# LNShield.net
KiCad netlist of a schematic drawn in EAGLE
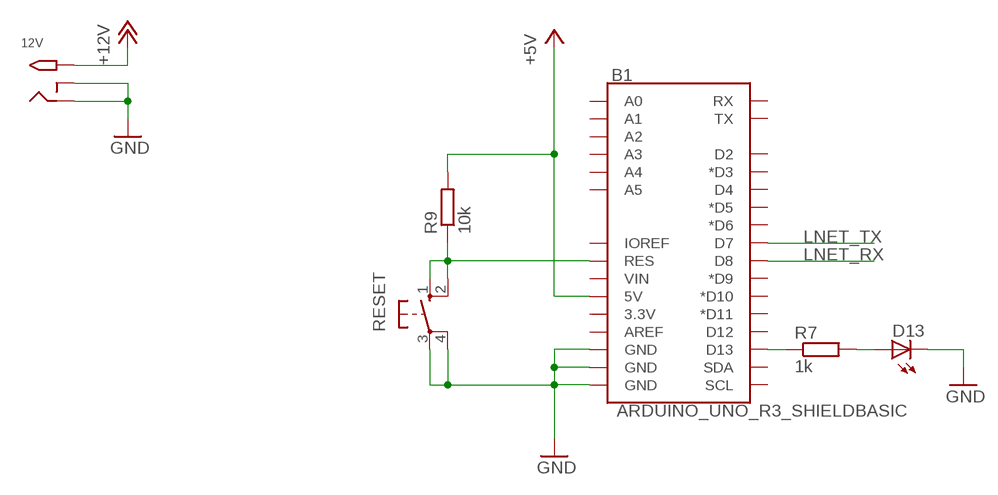
[diagram p0: schematic, sheet 1]
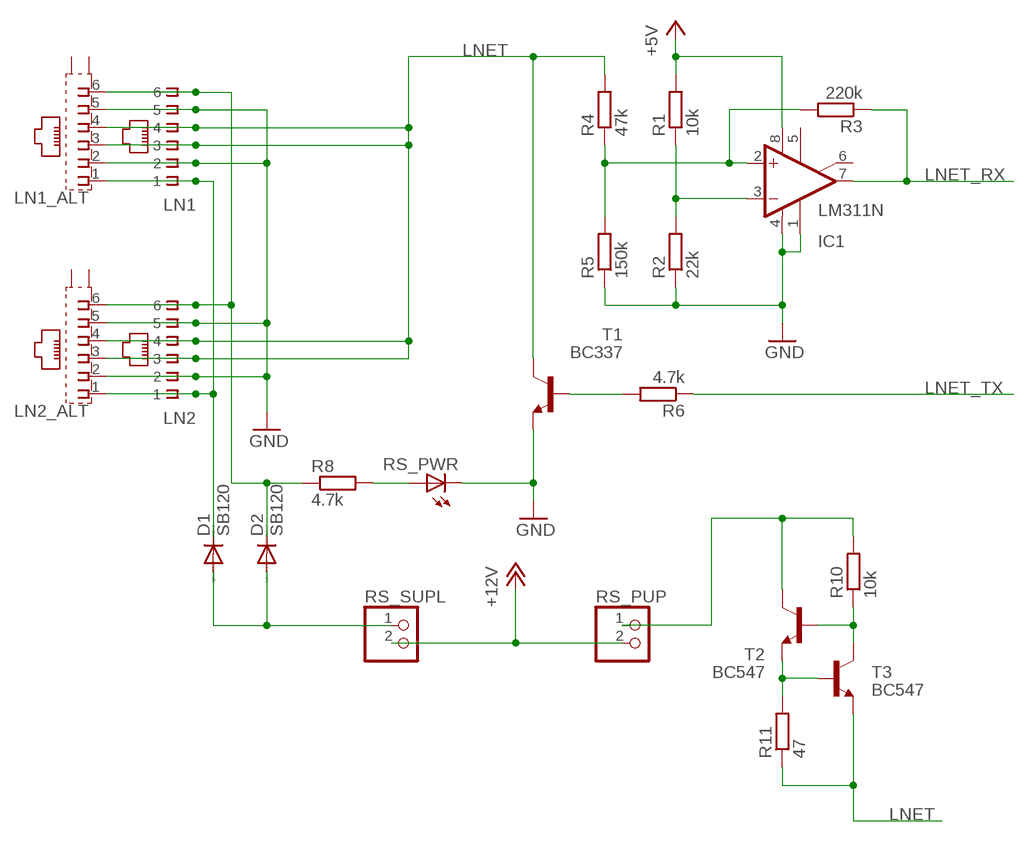
[diagram p1: schematic, sheet 2]

(export (version "E")
  (design (tool "Eeschema 10.0.6"))
  (components
    (comp (ref "12V")
      (value "2.1MMJACKTHM")
      (footprint "eagle-import:PJ-102A")
      (libsource (lib "eagle-import") (part "2.1MMJACKTHM"))
    )
    (comp (ref "B1")
      (value "ARDUINO_UNO_R3_SHIELDBASIC")
      (footprint "eagle-import:UNO_R3_SHIELD")
      (libsource (lib "eagle-import") (part "ARDUINO_UNO_R3_SHIELDBASIC"))
    )
    (comp (ref "D13")
      (value "LED3MM")
      (footprint "eagle-import:LED3MM")
      (libsource (lib "eagle-import") (part "LED3MM"))
    )
    (comp (ref "R7")
      (value "1k")
      (footprint "eagle-import:0207_2V")
      (libsource (lib "eagle-import") (part "R-EU_0207/2V"))
    )
    (comp (ref "R9")
      (value "10k")
      (footprint "eagle-import:0207_2V")
      (libsource (lib "eagle-import") (part "R-EU_0207/2V"))
    )
    (comp (ref "RESET")
      (value "10-XX")
      (footprint "eagle-import:B3F-10XX")
      (fields (field (name "MPN") "B3F-1000"))
      (libsource (lib "eagle-import") (part "10-XX"))
    )
    (comp (ref "D1")
      (value "SB120")
      (footprint "eagle-import:DO41-10")
      (libsource (lib "eagle-import") (part "SB120"))
    )
    (comp (ref "D2")
      (value "SB120")
      (footprint "eagle-import:DO41-10")
      (libsource (lib "eagle-import") (part "SB120"))
    )
    (comp (ref "IC1")
      (value "LM311N")
      (footprint "eagle-import:DIL08")
      (libsource (lib "eagle-import") (part "LM311N"))
    )
    (comp (ref "LN1")
      (value "RJ11-6X")
      (footprint "eagle-import:RJ11-NO_SHIELD")
      (libsource (lib "eagle-import") (part "RJ11-6X"))
    )
    (comp (ref "LN1_ALT")
      (value "YH-55-10")
      (footprint "eagle-import:YH-55-10")
      (libsource (lib "eagle-import") (part "YH-55-10"))
    )
    (comp (ref "LN2")
      (value "RJ11-6X")
      (footprint "eagle-import:RJ11-NO_SHIELD")
      (libsource (lib "eagle-import") (part "RJ11-6X"))
    )
    (comp (ref "LN2_ALT")
      (value "YH-55-10")
      (footprint "eagle-import:YH-55-10")
      (libsource (lib "eagle-import") (part "YH-55-10"))
    )
    (comp (ref "R1")
      (value "10k")
      (footprint "eagle-import:0207_2V")
      (libsource (lib "eagle-import") (part "R-EU_0207/2V"))
    )
    (comp (ref "R2")
      (value "22k")
      (footprint "eagle-import:0207_2V")
      (libsource (lib "eagle-import") (part "R-EU_0207/2V"))
    )
    (comp (ref "R3")
      (value "220k")
      (footprint "eagle-import:0207_2V")
      (libsource (lib "eagle-import") (part "R-EU_0207/2V"))
    )
    (comp (ref "R4")
      (value "47k")
      (footprint "eagle-import:0207_2V")
      (libsource (lib "eagle-import") (part "R-EU_0207/2V"))
    )
    (comp (ref "R5")
      (value "150k")
      (footprint "eagle-import:0207_2V")
      (libsource (lib "eagle-import") (part "R-EU_0207/2V"))
    )
    (comp (ref "R6")
      (value "4.7k")
      (footprint "eagle-import:0207_2V")
      (libsource (lib "eagle-import") (part "R-EU_0207/2V"))
    )
    (comp (ref "R8")
      (value "4.7k")
      (footprint "eagle-import:0207_2V")
      (libsource (lib "eagle-import") (part "R-EU_0207/2V"))
    )
    (comp (ref "R10")
      (value "10k")
      (footprint "eagle-import:0207_2V")
      (libsource (lib "eagle-import") (part "R-EU_0207/2V"))
    )
    (comp (ref "R11")
      (value "47")
      (footprint "eagle-import:0207_2V")
      (libsource (lib "eagle-import") (part "R-EU_0207/2V"))
    )
    (comp (ref "RS_PUP")
      (value "PINHD-1X2")
      (footprint "eagle-import:1X02")
      (libsource (lib "eagle-import") (part "PINHD-1X2"))
    )
    (comp (ref "RS_PWR")
      (value "LED3MM")
      (footprint "eagle-import:LED3MM")
      (libsource (lib "eagle-import") (part "LED3MM"))
    )
    (comp (ref "RS_SUPL")
      (value "PINHD-1X2")
      (footprint "eagle-import:1X02")
      (libsource (lib "eagle-import") (part "PINHD-1X2"))
    )
    (comp (ref "T1")
      (value "BC337")
      (footprint "eagle-import:TO92")
      (libsource (lib "eagle-import") (part "BC337"))
    )
    (comp (ref "T2")
      (value "BC547")
      (footprint "eagle-import:TO92")
      (libsource (lib "eagle-import") (part "BC547"))
    )
    (comp (ref "T3")
      (value "BC547")
      (footprint "eagle-import:TO92")
      (libsource (lib "eagle-import") (part "BC547"))
    )
  )
  (nets
    (net (code "1") (name "+5V") (class "Default")
      (node (ref "B1") (pin "5V") (pinfunction "5V_5V") (pintype "bidirectional"))
      (node (ref "IC1") (pin "8") (pinfunction "V+_8") (pintype "power_in"))
      (node (ref "R1") (pin "2") (pinfunction "2_2") (pintype "passive"))
      (node (ref "R9") (pin "2") (pinfunction "2_2") (pintype "passive"))
    )
    (net (code "2") (name "+12V") (class "Default")
      (node (ref "12V") (pin "TIP") (pinfunction "TIP_TIP") (pintype "bidirectional"))
      (node (ref "RS_PUP") (pin "2") (pinfunction "2_2") (pintype "passive"))
      (node (ref "RS_SUPL") (pin "2") (pinfunction "2_2") (pintype "passive"))
    )
    (net (code "3") (name "GND") (class "Default")
      (node (ref "12V") (pin "RING") (pinfunction "RING_RING") (pintype "bidirectional"))
      (node (ref "12V") (pin "RING_SW") (pinfunction "RING_SW_RING_SW") (pintype "bidirectional"))
      (node (ref "B1") (pin "GND@0") (pinfunction "GND_GND@0") (pintype "bidirectional"))
      (node (ref "B1") (pin "GND@1") (pinfunction "GND_GND@1") (pintype "bidirectional"))
      (node (ref "B1") (pin "GND@2") (pinfunction "GND_GND@2") (pintype "bidirectional"))
      (node (ref "D13") (pin "K") (pinfunction "C_K") (pintype "passive"))
      (node (ref "IC1") (pin "1") (pinfunction "GND_1") (pintype "passive"))
      (node (ref "IC1") (pin "4") (pinfunction "V-_4") (pintype "power_in"))
      (node (ref "LN1") (pin "2") (pinfunction "2_2") (pintype "passive"))
      (node (ref "LN1") (pin "5") (pinfunction "5_5") (pintype "passive"))
      (node (ref "LN1_ALT") (pin "2") (pinfunction "2_2") (pintype "passive"))
      (node (ref "LN1_ALT") (pin "5") (pinfunction "5_5") (pintype "passive"))
      (node (ref "LN2") (pin "2") (pinfunction "2_2") (pintype "passive"))
      (node (ref "LN2") (pin "5") (pinfunction "5_5") (pintype "passive"))
      (node (ref "LN2_ALT") (pin "2") (pinfunction "2_2") (pintype "passive"))
      (node (ref "LN2_ALT") (pin "5") (pinfunction "5_5") (pintype "passive"))
      (node (ref "R2") (pin "1") (pinfunction "1_1") (pintype "passive"))
      (node (ref "R5") (pin "1") (pinfunction "1_1") (pintype "passive"))
      (node (ref "RESET") (pin "3") (pinfunction "P_3") (pintype "passive"))
      (node (ref "RESET") (pin "4") (pinfunction "P1_4") (pintype "passive"))
      (node (ref "RS_PWR") (pin "K") (pinfunction "C_K") (pintype "passive"))
      (node (ref "T1") (pin "1") (pinfunction "E_1") (pintype "passive"))
    )
    (net (code "4") (name "LNET") (class "Default")
      (node (ref "LN1") (pin "3") (pinfunction "3_3") (pintype "passive"))
      (node (ref "LN1") (pin "4") (pinfunction "4_4") (pintype "passive"))
      (node (ref "LN1_ALT") (pin "3") (pinfunction "3_3") (pintype "passive"))
      (node (ref "LN1_ALT") (pin "4") (pinfunction "4_4") (pintype "passive"))
      (node (ref "LN2") (pin "3") (pinfunction "3_3") (pintype "passive"))
      (node (ref "LN2") (pin "4") (pinfunction "4_4") (pintype "passive"))
      (node (ref "LN2_ALT") (pin "3") (pinfunction "3_3") (pintype "passive"))
      (node (ref "LN2_ALT") (pin "4") (pinfunction "4_4") (pintype "passive"))
      (node (ref "R11") (pin "1") (pinfunction "1_1") (pintype "passive"))
      (node (ref "R4") (pin "2") (pinfunction "2_2") (pintype "passive"))
      (node (ref "T1") (pin "3") (pinfunction "C_3") (pintype "passive"))
      (node (ref "T3") (pin "1") (pinfunction "E_1") (pintype "passive"))
    )
    (net (code "5") (name "LNET_RX") (class "Default")
      (node (ref "B1") (pin "D8") (pinfunction "D8_D8") (pintype "bidirectional"))
      (node (ref "IC1") (pin "7") (pinfunction "OUT_7") (pintype "output"))
      (node (ref "R3") (pin "1") (pinfunction "1_1") (pintype "passive"))
    )
    (net (code "6") (name "LNET_TX") (class "Default")
      (node (ref "B1") (pin "D7") (pinfunction "D7_D7") (pintype "bidirectional"))
      (node (ref "R6") (pin "1") (pinfunction "1_1") (pintype "passive"))
    )
    (net (code "7") (name "Net-(B1-PadD13)") (class "Default")
      (node (ref "B1") (pin "D13") (pinfunction "D13_D13") (pintype "bidirectional"))
      (node (ref "R7") (pin "1") (pinfunction "1_1") (pintype "passive"))
    )
    (net (code "8") (name "Net-(D1-PadA)") (class "Default")
      (node (ref "D1") (pin "A") (pinfunction "A_A") (pintype "passive"))
      (node (ref "D2") (pin "A") (pinfunction "A_A") (pintype "passive"))
      (node (ref "RS_SUPL") (pin "1") (pinfunction "1_1") (pintype "passive"))
    )
    (net (code "9") (name "Net-(D1-PadC)") (class "Default")
      (node (ref "D1") (pin "C") (pinfunction "C_C") (pintype "passive"))
      (node (ref "LN1") (pin "1") (pinfunction "1_1") (pintype "passive"))
      (node (ref "LN1_ALT") (pin "1") (pinfunction "1_1") (pintype "passive"))
      (node (ref "LN2") (pin "1") (pinfunction "1_1") (pintype "passive"))
      (node (ref "LN2_ALT") (pin "1") (pinfunction "1_1") (pintype "passive"))
    )
    (net (code "10") (name "Net-(D2-PadC)") (class "Default")
      (node (ref "D2") (pin "C") (pinfunction "C_C") (pintype "passive"))
      (node (ref "LN1") (pin "6") (pinfunction "6_6") (pintype "passive"))
      (node (ref "LN1_ALT") (pin "6") (pinfunction "6_6") (pintype "passive"))
      (node (ref "LN2") (pin "6") (pinfunction "6_6") (pintype "passive"))
      (node (ref "LN2_ALT") (pin "6") (pinfunction "6_6") (pintype "passive"))
      (node (ref "R8") (pin "1") (pinfunction "1_1") (pintype "passive"))
    )
    (net (code "11") (name "Net-(D13-PadA)") (class "Default")
      (node (ref "D13") (pin "A") (pinfunction "A_A") (pintype "passive"))
      (node (ref "R7") (pin "2") (pinfunction "2_2") (pintype "passive"))
    )
    (net (code "12") (name "Net-(IC1-+IN)") (class "Default")
      (node (ref "IC1") (pin "2") (pinfunction "+IN_2") (pintype "input"))
      (node (ref "R3") (pin "2") (pinfunction "2_2") (pintype "passive"))
      (node (ref "R4") (pin "1") (pinfunction "1_1") (pintype "passive"))
      (node (ref "R5") (pin "2") (pinfunction "2_2") (pintype "passive"))
    )
    (net (code "13") (name "Net-(IC1--IN)") (class "Default")
      (node (ref "IC1") (pin "3") (pinfunction "-IN_3") (pintype "input"))
      (node (ref "R1") (pin "1") (pinfunction "1_1") (pintype "passive"))
      (node (ref "R2") (pin "2") (pinfunction "2_2") (pintype "passive"))
    )
    (net (code "14") (name "Net-(R8-Pad2)") (class "Default")
      (node (ref "R8") (pin "2") (pinfunction "2_2") (pintype "passive"))
      (node (ref "RS_PWR") (pin "A") (pinfunction "A_A") (pintype "passive"))
    )
    (net (code "15") (name "Net-(RESET-S)") (class "Default")
      (node (ref "B1") (pin "RES") (pinfunction "RES_RES") (pintype "bidirectional"))
      (node (ref "R9") (pin "1") (pinfunction "1_1") (pintype "passive"))
      (node (ref "RESET") (pin "1") (pinfunction "S_1") (pintype "passive"))
      (node (ref "RESET") (pin "2") (pinfunction "S1_2") (pintype "passive"))
    )
    (net (code "16") (name "Net-(T1-B)") (class "Default")
      (node (ref "R6") (pin "2") (pinfunction "2_2") (pintype "passive"))
      (node (ref "T1") (pin "2") (pinfunction "B_2") (pintype "passive"))
    )
    (net (code "17") (name "Net-(T2-B)") (class "Default")
      (node (ref "R10") (pin "1") (pinfunction "1_1") (pintype "passive"))
      (node (ref "T2") (pin "2") (pinfunction "B_2") (pintype "passive"))
      (node (ref "T3") (pin "3") (pinfunction "C_3") (pintype "passive"))
    )
    (net (code "18") (name "Net-(T2-C)") (class "Default")
      (node (ref "R10") (pin "2") (pinfunction "2_2") (pintype "passive"))
      (node (ref "RS_PUP") (pin "1") (pinfunction "1_1") (pintype "passive"))
      (node (ref "T2") (pin "3") (pinfunction "C_3") (pintype "passive"))
    )
    (net (code "19") (name "Net-(T2-E)") (class "Default")
      (node (ref "R11") (pin "2") (pinfunction "2_2") (pintype "passive"))
      (node (ref "T2") (pin "1") (pinfunction "E_1") (pintype "passive"))
      (node (ref "T3") (pin "2") (pinfunction "B_2") (pintype "passive"))
    )
    (net (code "20") (name "unconnected-(B1-*D3-PadD3)") (class "Default")
      (node (ref "B1") (pin "D3") (pinfunction "*D3_D3") (pintype "bidirectional"))
    )
    (net (code "21") (name "unconnected-(B1-*D5-PadD5)") (class "Default")
      (node (ref "B1") (pin "D5") (pinfunction "*D5_D5") (pintype "bidirectional"))
    )
    (net (code "22") (name "unconnected-(B1-*D6-PadD6)") (class "Default")
      (node (ref "B1") (pin "D6") (pinfunction "*D6_D6") (pintype "bidirectional"))
    )
    (net (code "23") (name "unconnected-(B1-*D9-PadD9)") (class "Default")
      (node (ref "B1") (pin "D9") (pinfunction "*D9_D9") (pintype "bidirectional"))
    )
    (net (code "24") (name "unconnected-(B1-*D10-PadD10)") (class "Default")
      (node (ref "B1") (pin "D10") (pinfunction "*D10_D10") (pintype "bidirectional"))
    )
    (net (code "25") (name "unconnected-(B1-*D11-PadD11)") (class "Default")
      (node (ref "B1") (pin "D11") (pinfunction "*D11_D11") (pintype "bidirectional"))
    )
    (net (code "26") (name "unconnected-(B1-Pad3.3V)") (class "Default")
      (node (ref "B1") (pin "3.3V") (pinfunction "3.3V_3.3V") (pintype "bidirectional"))
    )
    (net (code "27") (name "unconnected-(B1-PadA0)") (class "Default")
      (node (ref "B1") (pin "A0") (pinfunction "A0_A0") (pintype "bidirectional"))
    )
    (net (code "28") (name "unconnected-(B1-PadA1)") (class "Default")
      (node (ref "B1") (pin "A1") (pinfunction "A1_A1") (pintype "bidirectional"))
    )
    (net (code "29") (name "unconnected-(B1-PadA2)") (class "Default")
      (node (ref "B1") (pin "A2") (pinfunction "A2_A2") (pintype "bidirectional"))
    )
    (net (code "30") (name "unconnected-(B1-PadA3)") (class "Default")
      (node (ref "B1") (pin "A3") (pinfunction "A3_A3") (pintype "bidirectional"))
    )
    (net (code "31") (name "unconnected-(B1-PadA4)") (class "Default")
      (node (ref "B1") (pin "A4") (pinfunction "A4_A4") (pintype "bidirectional"))
    )
    (net (code "32") (name "unconnected-(B1-PadA5)") (class "Default")
      (node (ref "B1") (pin "A5") (pinfunction "A5_A5") (pintype "bidirectional"))
    )
    (net (code "33") (name "unconnected-(B1-PadAREF)") (class "Default")
      (node (ref "B1") (pin "AREF") (pinfunction "AREF_AREF") (pintype "bidirectional"))
    )
    (net (code "34") (name "unconnected-(B1-PadD2)") (class "Default")
      (node (ref "B1") (pin "D2") (pinfunction "D2_D2") (pintype "bidirectional"))
    )
    (net (code "35") (name "unconnected-(B1-PadD4)") (class "Default")
      (node (ref "B1") (pin "D4") (pinfunction "D4_D4") (pintype "bidirectional"))
    )
    (net (code "36") (name "unconnected-(B1-PadD12)") (class "Default")
      (node (ref "B1") (pin "D12") (pinfunction "D12_D12") (pintype "bidirectional"))
    )
    (net (code "37") (name "unconnected-(B1-PadIOREF)") (class "Default")
      (node (ref "B1") (pin "IOREF") (pinfunction "IOREF_IOREF") (pintype "bidirectional"))
    )
    (net (code "38") (name "unconnected-(B1-PadRX)") (class "Default")
      (node (ref "B1") (pin "RX") (pinfunction "RX_RX") (pintype "bidirectional"))
    )
    (net (code "39") (name "unconnected-(B1-PadSCL)") (class "Default")
      (node (ref "B1") (pin "SCL") (pinfunction "SCL_SCL") (pintype "bidirectional"))
    )
    (net (code "40") (name "unconnected-(B1-PadSDA)") (class "Default")
      (node (ref "B1") (pin "SDA") (pinfunction "SDA_SDA") (pintype "bidirectional"))
    )
    (net (code "41") (name "unconnected-(B1-PadTX)") (class "Default")
      (node (ref "B1") (pin "TX") (pinfunction "TX_TX") (pintype "bidirectional"))
    )
    (net (code "42") (name "unconnected-(B1-PadVIN)") (class "Default")
      (node (ref "B1") (pin "VIN") (pinfunction "VIN_VIN") (pintype "bidirectional"))
    )
    (net (code "43") (name "unconnected-(IC1-ON-Pad5)") (class "Default")
      (node (ref "IC1") (pin "5") (pinfunction "ON_5") (pintype "passive"))
    )
    (net (code "44") (name "unconnected-(IC1-ON{slash}STR-Pad6)") (class "Default")
      (node (ref "IC1") (pin "6") (pinfunction "ON/STR_6") (pintype "passive"))
    )
    (net (code "45") (name "unconnected-(LN1_ALT-S-PadS1)") (class "Default")
      (node (ref "LN1_ALT") (pin "S1") (pinfunction "S_S1") (pintype "passive"))
    )
    (net (code "46") (name "unconnected-(LN1_ALT-S-PadS2)") (class "Default")
      (node (ref "LN1_ALT") (pin "S2") (pinfunction "S_S2") (pintype "passive"))
    )
    (net (code "47") (name "unconnected-(LN2_ALT-S-PadS1)") (class "Default")
      (node (ref "LN2_ALT") (pin "S1") (pinfunction "S_S1") (pintype "passive"))
    )
    (net (code "48") (name "unconnected-(LN2_ALT-S-PadS2)") (class "Default")
      (node (ref "LN2_ALT") (pin "S2") (pinfunction "S_S2") (pintype "passive"))
    )
  )
)
